# Adafruit_QT_Py.net
KiCad netlist of a schematic drawn in EAGLE
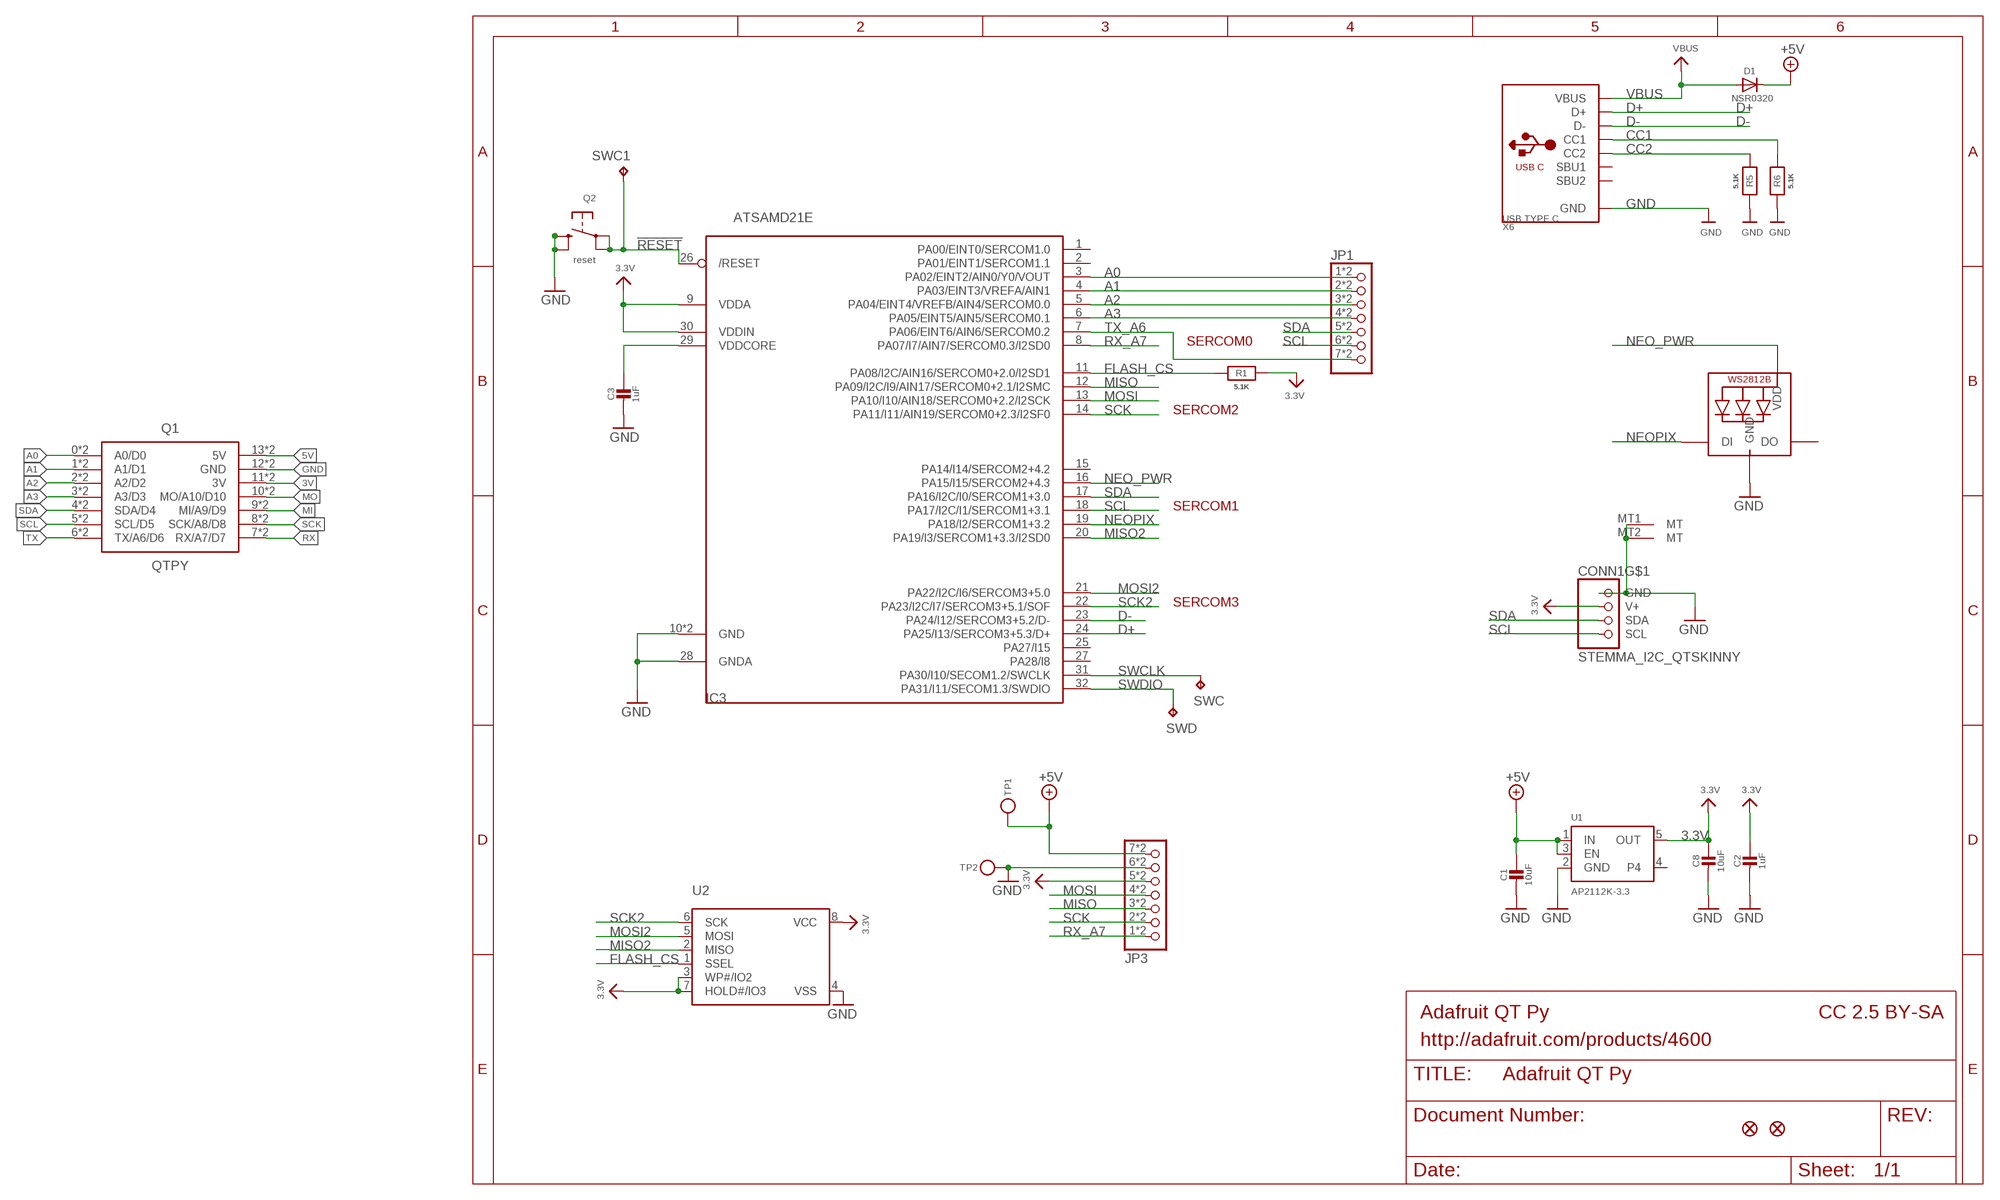
[diagram p0: schematic, sheet 1]

(export (version "E")
  (design (tool "Eeschema 10.0.6"))
  (components
    (comp (ref "C1")
      (value "10uF")
      (footprint "eagle-import:_0805MP")
      (libsource (lib "eagle-import") (part "CAP_CERAMIC_0805MP"))
    )
    (comp (ref "C2")
      (value "1uF")
      (footprint "eagle-import:_0402NO")
      (libsource (lib "eagle-import") (part "CAP_CERAMIC_0402NO"))
    )
    (comp (ref "C3")
      (value "1uF")
      (footprint "eagle-import:_0402NO")
      (libsource (lib "eagle-import") (part "CAP_CERAMIC_0402NO"))
    )
    (comp (ref "C8")
      (value "10uF")
      (footprint "eagle-import:_0805MP")
      (libsource (lib "eagle-import") (part "CAP_CERAMIC_0805MP"))
    )
    (comp (ref "CONN1")
      (value "STEMMA_I2C_QTSKINNY")
      (footprint "eagle-import:JST_SH4_SKINNY")
      (libsource (lib "eagle-import") (part "STEMMA_I2C_QTSKINNY"))
    )
    (comp (ref "D1")
      (value "NSR0320")
      (footprint "eagle-import:SOD-323_MINI")
      (libsource (lib "eagle-import") (part "DIODE_SOD323MINI"))
    )
    (comp (ref "IC3")
      (value "ATSAMD21E")
      (footprint "eagle-import:QFN32_5MM")
      (libsource (lib "eagle-import") (part "ATSAMD21E"))
    )
    (comp (ref "JP1")
      (value "HEADER-1X7_CASTEL")
      (footprint "eagle-import:1X07_CASTEL")
      (libsource (lib "eagle-import") (part "HEADER-1X7_CASTEL"))
    )
    (comp (ref "JP3")
      (value "HEADER-1X7_CASTEL")
      (footprint "eagle-import:1X07_CASTEL")
      (libsource (lib "eagle-import") (part "HEADER-1X7_CASTEL"))
    )
    (comp (ref "LED1")
      (value "WS2812B_SK6805_1515")
      (footprint "eagle-import:SK6805_1515")
      (libsource (lib "eagle-import") (part "WS2812B_SK6805_1515"))
    )
    (comp (ref "Q1")
      (value "QTPY")
      (footprint "eagle-import:QTPY")
      (libsource (lib "eagle-import") (part "QTPY"))
    )
    (comp (ref "Q2")
      (value "reset")
      (footprint "eagle-import:BTN_KMR2_4.6X2.8")
      (libsource (lib "eagle-import") (part "SWITCH_TACT_SMT4.6X2.8"))
    )
    (comp (ref "R1")
      (value "5.1K")
      (footprint "eagle-import:_0402NO")
      (libsource (lib "eagle-import") (part "RESISTOR_0402NO"))
    )
    (comp (ref "R5")
      (value "5.1K")
      (footprint "eagle-import:_0402NO")
      (libsource (lib "eagle-import") (part "RESISTOR_0402NO"))
    )
    (comp (ref "R6")
      (value "5.1K")
      (footprint "eagle-import:_0402NO")
      (libsource (lib "eagle-import") (part "RESISTOR_0402NO"))
    )
    (comp (ref "SWC")
      (value "TPB1,27")
      (footprint "eagle-import:B1,27")
      (libsource (lib "eagle-import") (part "TPB1,27"))
    )
    (comp (ref "SWC1")
      (value "TPB1,27")
      (footprint "eagle-import:B1,27")
      (libsource (lib "eagle-import") (part "TPB1,27"))
    )
    (comp (ref "SWD")
      (value "TPB1,27")
      (footprint "eagle-import:B1,27")
      (libsource (lib "eagle-import") (part "TPB1,27"))
    )
    (comp (ref "TP1")
      (value "TESTPOINT_1X3")
      (footprint "eagle-import:TESTPOINT_RECT_1X3MM")
      (libsource (lib "eagle-import") (part "TESTPOINT_1X3"))
    )
    (comp (ref "TP2")
      (value "TESTPOINT_1X3")
      (footprint "eagle-import:TESTPOINT_RECT_1X3MM")
      (libsource (lib "eagle-import") (part "TESTPOINT_1X3"))
    )
    (comp (ref "U$6")
      (value "FIDUCIAL_1MM")
      (footprint "eagle-import:FIDUCIAL_1MM")
      (libsource (lib "eagle-import") (part "FIDUCIAL_1MM"))
    )
    (comp (ref "U$8")
      (value "FIDUCIAL_1MM")
      (footprint "eagle-import:FIDUCIAL_1MM")
      (libsource (lib "eagle-import") (part "FIDUCIAL_1MM"))
    )
    (comp (ref "U1")
      (value "AP2112K-3.3")
      (footprint "eagle-import:SOT23-5")
      (libsource (lib "eagle-import") (part "VREG_SOT23-5"))
    )
    (comp (ref "U2")
      (value "SPIFLASH_8PIN")
      (footprint "eagle-import:SOIC8_150MIL")
      (libsource (lib "eagle-import") (part "SPIFLASH_8PIN"))
    )
    (comp (ref "X6")
      (value "USB TYPE C")
      (footprint "eagle-import:USB_C_CUSB31-CFM2AX-01-X")
      (libsource (lib "eagle-import") (part "USB_C"))
    )
  )
  (nets
    (net (code "1") (name "+5V") (class "Default")
      (node (ref "C1") (pin "1") (pinfunction "1_1") (pintype "passive"))
      (node (ref "D1") (pin "C") (pinfunction "C_C") (pintype "passive"))
      (node (ref "JP3") (pin "7") (pinfunction "7_7") (pintype "passive"))
      (node (ref "JP3") (pin "7C") (pinfunction "7_7C") (pintype "passive"))
      (node (ref "TP1") (pin "P$1") (pinfunction "P$1_P$1") (pintype "bidirectional"))
      (node (ref "U1") (pin "1") (pinfunction "IN_1") (pintype "power_in"))
      (node (ref "U1") (pin "3") (pinfunction "EN_3") (pintype "input"))
    )
    (net (code "2") (name "/CC1") (class "Default")
      (node (ref "R6") (pin "2") (pinfunction "2_2") (pintype "passive"))
      (node (ref "X6") (pin "A5") (pinfunction "CC1_A5") (pintype "bidirectional"))
    )
    (net (code "3") (name "/CC2") (class "Default")
      (node (ref "R5") (pin "2") (pinfunction "2_2") (pintype "passive"))
      (node (ref "X6") (pin "B5") (pinfunction "CC2_B5") (pintype "bidirectional"))
    )
    (net (code "4") (name "/D+") (class "Default")
      (node (ref "IC3") (pin "24") (pinfunction "PA25/I13/SERCOM3+5.3/D+_24") (pintype "bidirectional"))
      (node (ref "X6") (pin "A6") (pinfunction "D+_A6") (pintype "bidirectional"))
      (node (ref "X6") (pin "B6") (pinfunction "D+_B6") (pintype "bidirectional"))
    )
    (net (code "5") (name "/D-") (class "Default")
      (node (ref "IC3") (pin "23") (pinfunction "PA24/I12/SERCOM3+5.2/D-_23") (pintype "bidirectional"))
      (node (ref "X6") (pin "A7") (pinfunction "D-_A7") (pintype "bidirectional"))
      (node (ref "X6") (pin "B7") (pinfunction "D-_B7") (pintype "bidirectional"))
    )
    (net (code "6") (name "/FLASH_CS") (class "Default")
      (node (ref "IC3") (pin "11") (pinfunction "PA08/I2C/AIN16/SERCOM0+2.0/I2SD1_11") (pintype "bidirectional"))
      (node (ref "R1") (pin "2") (pinfunction "2_2") (pintype "passive"))
      (node (ref "U2") (pin "1") (pinfunction "SSEL_1") (pintype "bidirectional"))
    )
    (net (code "7") (name "/MISO") (class "Default")
      (node (ref "IC3") (pin "12") (pinfunction "PA09/I2C/I9/AIN17/SERCOM0+2.1/I2SMC_12") (pintype "bidirectional"))
      (node (ref "JP3") (pin "3") (pinfunction "3_3") (pintype "passive"))
      (node (ref "JP3") (pin "3C") (pinfunction "3_3C") (pintype "passive"))
    )
    (net (code "8") (name "/MISO2") (class "Default")
      (node (ref "IC3") (pin "20") (pinfunction "PA19/I3/SERCOM1+3.3/I2SD0_20") (pintype "bidirectional"))
      (node (ref "U2") (pin "2") (pinfunction "MISO_2") (pintype "bidirectional"))
    )
    (net (code "9") (name "/MOSI") (class "Default")
      (node (ref "IC3") (pin "13") (pinfunction "PA10/I10/AIN18/SERCOM0+2.2/I2SCK_13") (pintype "bidirectional"))
      (node (ref "JP3") (pin "4") (pinfunction "4_4") (pintype "passive"))
      (node (ref "JP3") (pin "4C") (pinfunction "4_4C") (pintype "passive"))
    )
    (net (code "10") (name "/MOSI2") (class "Default")
      (node (ref "IC3") (pin "21") (pinfunction "PA22/I2C/I6/SERCOM3+5.0_21") (pintype "bidirectional"))
      (node (ref "U2") (pin "5") (pinfunction "MOSI_5") (pintype "bidirectional"))
    )
    (net (code "11") (name "/NEOPIX") (class "Default")
      (node (ref "IC3") (pin "19") (pinfunction "PA18/I2/SERCOM1+3.2_19") (pintype "bidirectional"))
      (node (ref "LED1") (pin "1") (pinfunction "DI_1") (pintype "input"))
    )
    (net (code "12") (name "/NEO_PWR") (class "Default")
      (node (ref "IC3") (pin "16") (pinfunction "PA15/I15/SERCOM2+4.3_16") (pintype "bidirectional"))
      (node (ref "LED1") (pin "2") (pinfunction "VDD_2") (pintype "power_in"))
    )
    (net (code "13") (name "/RX_A7") (class "Default")
      (node (ref "IC3") (pin "8") (pinfunction "PA07/I7/AIN7/SERCOM0.3/I2SD0_8") (pintype "bidirectional"))
      (node (ref "JP3") (pin "1") (pinfunction "1_1") (pintype "passive"))
      (node (ref "JP3") (pin "1C") (pinfunction "1_1C") (pintype "passive"))
    )
    (net (code "14") (name "/SCK2") (class "Default")
      (node (ref "IC3") (pin "22") (pinfunction "PA23/I2C/I7/SERCOM3+5.1/SOF_22") (pintype "bidirectional"))
      (node (ref "U2") (pin "6") (pinfunction "SCK_6") (pintype "bidirectional"))
    )
    (net (code "15") (name "/SWCLK") (class "Default")
      (node (ref "IC3") (pin "31") (pinfunction "PA30/I10/SECOM1.2/SWCLK_31") (pintype "bidirectional"))
      (node (ref "SWC") (pin "TP") (pinfunction "TP_TP") (pintype "input"))
    )
    (net (code "16") (name "/SWDIO") (class "Default")
      (node (ref "IC3") (pin "32") (pinfunction "PA31/I11/SECOM1.3/SWDIO_32") (pintype "bidirectional"))
      (node (ref "SWD") (pin "TP") (pinfunction "TP_TP") (pintype "input"))
    )
    (net (code "17") (name "/TX_A6") (class "Default")
      (node (ref "IC3") (pin "7") (pinfunction "PA06/EINT6/AIN6/SERCOM0.2_7") (pintype "bidirectional"))
      (node (ref "JP1") (pin "7") (pinfunction "7_7") (pintype "passive"))
      (node (ref "JP1") (pin "7C") (pinfunction "7_7C") (pintype "passive"))
    )
    (net (code "18") (name "/~{RESET}") (class "Default")
      (node (ref "IC3") (pin "26") (pinfunction "/RESET_26") (pintype "bidirectional"))
      (node (ref "Q2") (pin "A") (pinfunction "P_A") (pintype "passive"))
      (node (ref "Q2") (pin "A'") (pinfunction "P1_A'") (pintype "passive"))
      (node (ref "SWC1") (pin "TP") (pinfunction "TP_TP") (pintype "input"))
    )
    (net (code "19") (name "3.3V") (class "Default")
      (node (ref "C2") (pin "1") (pinfunction "1_1") (pintype "passive"))
      (node (ref "C8") (pin "1") (pinfunction "1_1") (pintype "passive"))
      (node (ref "CONN1") (pin "2") (pinfunction "V+_2") (pintype "passive"))
      (node (ref "IC3") (pin "30") (pinfunction "VDDIN_30") (pintype "power_in"))
      (node (ref "IC3") (pin "9") (pinfunction "VDDA_9") (pintype "power_in"))
      (node (ref "JP3") (pin "5") (pinfunction "5_5") (pintype "passive"))
      (node (ref "JP3") (pin "5C") (pinfunction "5_5C") (pintype "passive"))
      (node (ref "R1") (pin "1") (pinfunction "1_1") (pintype "passive"))
      (node (ref "U1") (pin "5") (pinfunction "OUT_5") (pintype "power_in"))
      (node (ref "U2") (pin "3") (pinfunction "WP#/IO2_3") (pintype "bidirectional"))
      (node (ref "U2") (pin "7") (pinfunction "HOLD#/IO3_7") (pintype "bidirectional"))
      (node (ref "U2") (pin "8") (pinfunction "VCC_8") (pintype "bidirectional"))
    )
    (net (code "20") (name "3V") (class "Default")
      (node (ref "Q1") (pin "11") (pinfunction "3V_11") (pintype "bidirectional"))
      (node (ref "Q1") (pin "11C") (pinfunction "3V_11C") (pintype "bidirectional"))
    )
    (net (code "21") (name "5V") (class "Default")
      (node (ref "Q1") (pin "13") (pinfunction "5V_13") (pintype "bidirectional"))
      (node (ref "Q1") (pin "13C") (pinfunction "5V_13C") (pintype "bidirectional"))
    )
    (net (code "22") (name "A0") (class "Default")
      (node (ref "IC3") (pin "3") (pinfunction "PA02/EINT2/AIN0/Y0/VOUT_3") (pintype "bidirectional"))
      (node (ref "JP1") (pin "1") (pinfunction "1_1") (pintype "passive"))
      (node (ref "JP1") (pin "1C") (pinfunction "1_1C") (pintype "passive"))
      (node (ref "Q1") (pin "0") (pinfunction "A0/D0_0") (pintype "bidirectional"))
      (node (ref "Q1") (pin "0C") (pinfunction "A0/D0_0C") (pintype "bidirectional"))
    )
    (net (code "23") (name "A1") (class "Default")
      (node (ref "IC3") (pin "4") (pinfunction "PA03/EINT3/VREFA/AIN1_4") (pintype "bidirectional"))
      (node (ref "JP1") (pin "2") (pinfunction "2_2") (pintype "passive"))
      (node (ref "JP1") (pin "2C") (pinfunction "2_2C") (pintype "passive"))
      (node (ref "Q1") (pin "1") (pinfunction "A1/D1_1") (pintype "bidirectional"))
      (node (ref "Q1") (pin "1C") (pinfunction "A1/D1_1C") (pintype "bidirectional"))
    )
    (net (code "24") (name "A2") (class "Default")
      (node (ref "IC3") (pin "5") (pinfunction "PA04/EINT4/VREFB/AIN4/SERCOM0.0_5") (pintype "bidirectional"))
      (node (ref "JP1") (pin "3") (pinfunction "3_3") (pintype "passive"))
      (node (ref "JP1") (pin "3C") (pinfunction "3_3C") (pintype "passive"))
      (node (ref "Q1") (pin "2") (pinfunction "A2/D2_2") (pintype "bidirectional"))
      (node (ref "Q1") (pin "2C") (pinfunction "A2/D2_2C") (pintype "bidirectional"))
    )
    (net (code "25") (name "A3") (class "Default")
      (node (ref "IC3") (pin "6") (pinfunction "PA05/EINT5/AIN5/SERCOM0.1_6") (pintype "bidirectional"))
      (node (ref "JP1") (pin "4") (pinfunction "4_4") (pintype "passive"))
      (node (ref "JP1") (pin "4C") (pinfunction "4_4C") (pintype "passive"))
      (node (ref "Q1") (pin "3") (pinfunction "A3/D3_3") (pintype "bidirectional"))
      (node (ref "Q1") (pin "3C") (pinfunction "A3/D3_3C") (pintype "bidirectional"))
    )
    (net (code "26") (name "GND") (class "Default")
      (node (ref "C1") (pin "2") (pinfunction "2_2") (pintype "passive"))
      (node (ref "C2") (pin "2") (pinfunction "2_2") (pintype "passive"))
      (node (ref "C3") (pin "2") (pinfunction "2_2") (pintype "passive"))
      (node (ref "C8") (pin "2") (pinfunction "2_2") (pintype "passive"))
      (node (ref "CONN1") (pin "1") (pinfunction "GND_1") (pintype "passive"))
      (node (ref "CONN1") (pin "MT1") (pinfunction "MT_MT1") (pintype "bidirectional"))
      (node (ref "CONN1") (pin "MT2") (pinfunction "MT_MT2") (pintype "bidirectional"))
      (node (ref "IC3") (pin "10") (pinfunction "GND_10") (pintype "power_in"))
      (node (ref "IC3") (pin "28") (pinfunction "GNDA_28") (pintype "power_in"))
      (node (ref "IC3") (pin "33") (pinfunction "GND_33") (pintype "power_in"))
      (node (ref "JP3") (pin "6") (pinfunction "6_6") (pintype "passive"))
      (node (ref "JP3") (pin "6C") (pinfunction "6_6C") (pintype "passive"))
      (node (ref "LED1") (pin "4") (pinfunction "GND_4") (pintype "power_in"))
      (node (ref "Q1") (pin "12") (pinfunction "GND_12") (pintype "bidirectional"))
      (node (ref "Q1") (pin "12C") (pinfunction "GND_12C") (pintype "bidirectional"))
      (node (ref "Q2") (pin "B") (pinfunction "S_B") (pintype "passive"))
      (node (ref "Q2") (pin "B'") (pinfunction "S1_B'") (pintype "passive"))
      (node (ref "R5") (pin "1") (pinfunction "1_1") (pintype "passive"))
      (node (ref "R6") (pin "1") (pinfunction "1_1") (pintype "passive"))
      (node (ref "TP2") (pin "P$1") (pinfunction "P$1_P$1") (pintype "bidirectional"))
      (node (ref "U1") (pin "2") (pinfunction "GND_2") (pintype "power_in"))
      (node (ref "U2") (pin "4") (pinfunction "VSS_4") (pintype "bidirectional"))
      (node (ref "X6") (pin "A1B12") (pinfunction "GND_A1B12") (pintype "power_in"))
      (node (ref "X6") (pin "B1A12") (pinfunction "GND_B1A12") (pintype "power_in"))
    )
    (net (code "27") (name "MI") (class "Default")
      (node (ref "Q1") (pin "9") (pinfunction "MI/A9/D9_9") (pintype "bidirectional"))
      (node (ref "Q1") (pin "9C") (pinfunction "MI/A9/D9_9C") (pintype "bidirectional"))
    )
    (net (code "28") (name "MO") (class "Default")
      (node (ref "Q1") (pin "10") (pinfunction "MO/A10/D10_10") (pintype "bidirectional"))
      (node (ref "Q1") (pin "10C") (pinfunction "MO/A10/D10_10C") (pintype "bidirectional"))
    )
    (net (code "29") (name "Net-(IC3-VDDCORE)") (class "Default")
      (node (ref "C3") (pin "1") (pinfunction "1_1") (pintype "passive"))
      (node (ref "IC3") (pin "29") (pinfunction "VDDCORE_29") (pintype "power_in"))
    )
    (net (code "30") (name "RX") (class "Default")
      (node (ref "Q1") (pin "7") (pinfunction "RX/A7/D7_7") (pintype "bidirectional"))
      (node (ref "Q1") (pin "7C") (pinfunction "RX/A7/D7_7C") (pintype "bidirectional"))
    )
    (net (code "31") (name "SCK") (class "Default")
      (node (ref "IC3") (pin "14") (pinfunction "PA11/I11/AIN19/SERCOM0+2.3/I2SF0_14") (pintype "bidirectional"))
      (node (ref "JP3") (pin "2") (pinfunction "2_2") (pintype "passive"))
      (node (ref "JP3") (pin "2C") (pinfunction "2_2C") (pintype "passive"))
      (node (ref "Q1") (pin "8") (pinfunction "SCK/A8/D8_8") (pintype "bidirectional"))
      (node (ref "Q1") (pin "8C") (pinfunction "SCK/A8/D8_8C") (pintype "bidirectional"))
    )
    (net (code "32") (name "SCL") (class "Default")
      (node (ref "CONN1") (pin "4") (pinfunction "SCL_4") (pintype "passive"))
      (node (ref "IC3") (pin "18") (pinfunction "PA17/I2C/I1/SERCOM1+3.1_18") (pintype "bidirectional"))
      (node (ref "JP1") (pin "6") (pinfunction "6_6") (pintype "passive"))
      (node (ref "JP1") (pin "6C") (pinfunction "6_6C") (pintype "passive"))
      (node (ref "Q1") (pin "5") (pinfunction "SCL/D5_5") (pintype "bidirectional"))
      (node (ref "Q1") (pin "5C") (pinfunction "SCL/D5_5C") (pintype "bidirectional"))
    )
    (net (code "33") (name "SDA") (class "Default")
      (node (ref "CONN1") (pin "3") (pinfunction "SDA_3") (pintype "passive"))
      (node (ref "IC3") (pin "17") (pinfunction "PA16/I2C/I0/SERCOM1+3.0_17") (pintype "bidirectional"))
      (node (ref "JP1") (pin "5") (pinfunction "5_5") (pintype "passive"))
      (node (ref "JP1") (pin "5C") (pinfunction "5_5C") (pintype "passive"))
      (node (ref "Q1") (pin "4") (pinfunction "SDA/D4_4") (pintype "bidirectional"))
      (node (ref "Q1") (pin "4C") (pinfunction "SDA/D4_4C") (pintype "bidirectional"))
    )
    (net (code "34") (name "TX") (class "Default")
      (node (ref "Q1") (pin "6") (pinfunction "TX/A6/D6_6") (pintype "bidirectional"))
      (node (ref "Q1") (pin "6C") (pinfunction "TX/A6/D6_6C") (pintype "bidirectional"))
    )
    (net (code "35") (name "VBUS") (class "Default")
      (node (ref "D1") (pin "A") (pinfunction "A_A") (pintype "passive"))
      (node (ref "X6") (pin "A4B9") (pinfunction "VBUS_A4B9") (pintype "power_in"))
      (node (ref "X6") (pin "B4A9") (pinfunction "VBUS_B4A9") (pintype "power_in"))
    )
    (net (code "36") (name "unconnected-(IC3-PA00{slash}EINT0{slash}SERCOM1.0-Pad1)") (class "Default")
      (node (ref "IC3") (pin "1") (pinfunction "PA00/EINT0/SERCOM1.0_1") (pintype "bidirectional"))
    )
    (net (code "37") (name "unconnected-(IC3-PA01{slash}EINT1{slash}SERCOM1.1-Pad2)") (class "Default")
      (node (ref "IC3") (pin "2") (pinfunction "PA01/EINT1/SERCOM1.1_2") (pintype "bidirectional"))
    )
    (net (code "38") (name "unconnected-(IC3-PA14{slash}I14{slash}SERCOM2+4.2-Pad15)") (class "Default")
      (node (ref "IC3") (pin "15") (pinfunction "PA14/I14/SERCOM2+4.2_15") (pintype "bidirectional"))
    )
    (net (code "39") (name "unconnected-(IC3-PA27{slash}I15-Pad25)") (class "Default")
      (node (ref "IC3") (pin "25") (pinfunction "PA27/I15_25") (pintype "bidirectional"))
    )
    (net (code "40") (name "unconnected-(IC3-PA28{slash}I8-Pad27)") (class "Default")
      (node (ref "IC3") (pin "27") (pinfunction "PA28/I8_27") (pintype "bidirectional"))
    )
    (net (code "41") (name "unconnected-(LED1-DO-Pad3)") (class "Default")
      (node (ref "LED1") (pin "3") (pinfunction "DO_3") (pintype "output"))
    )
    (net (code "42") (name "unconnected-(U1-P4-Pad4)") (class "Default")
      (node (ref "U1") (pin "4") (pinfunction "P4_4") (pintype "bidirectional"))
    )
    (net (code "43") (name "unconnected-(X6-SBU1-PadA8)") (class "Default")
      (node (ref "X6") (pin "A8") (pinfunction "SBU1_A8") (pintype "bidirectional"))
    )
    (net (code "44") (name "unconnected-(X6-SBU2-PadB8)") (class "Default")
      (node (ref "X6") (pin "B8") (pinfunction "SBU2_B8") (pintype "bidirectional"))
    )
  )
)
